# BlockDiagram.net
KiCad netlist of a schematic drawn in Altium Designer
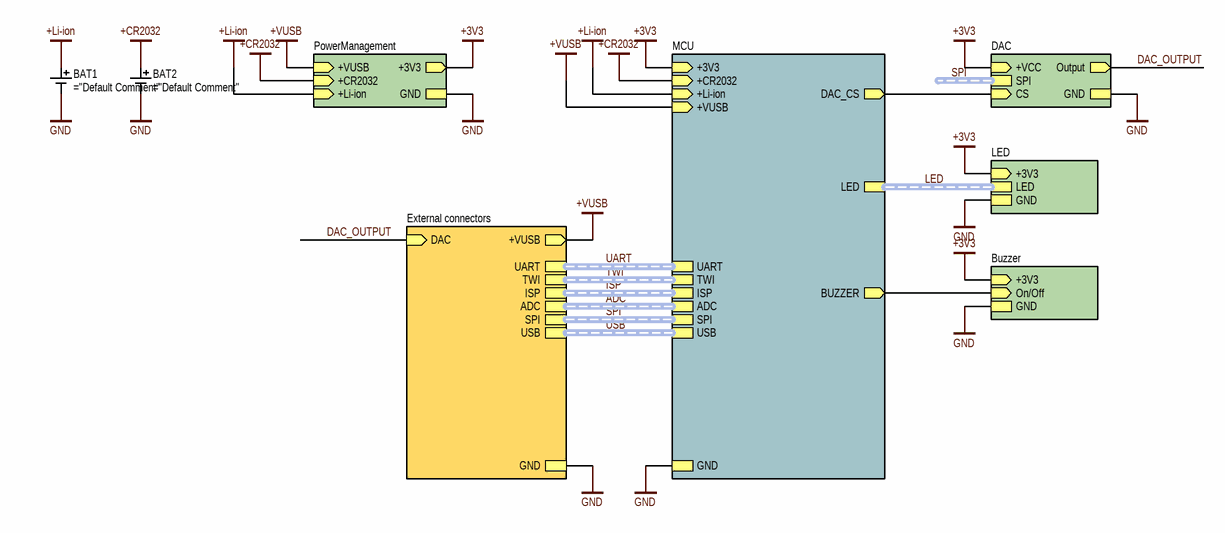
[diagram p0: BlockDiagram.SchDoc]

(export (version "E")
  (design (tool "Eeschema 10.0.6"))
  (components
    (comp (ref "BAT1")
      (value "~")
      (description "CONN HEADER R/A 2POS 2MM")
      (fields (field (name "TOLERANCE") "* %") (field (name "MANUFACTURER") "JST Sales America Inc."))
      (libsource (lib "femtoino") (part "S2B-PH-K-S(LF)(SN)"))
    )
    (comp (ref "BAT2")
      (value "~")
      (description "BATT HOLDER COIN 20MM 1 CELL SMD")
      (fields
        (field (name "TOLERANCE") "* %")
        (field (name "MANUFACTURER") "MPD (Memory Protection Devices)")
      )
      (libsource (lib "femtoino") (part "BU2032SM-HD-G"))
    )
  )
  (nets
    (net (code "9") (name "+CR2032") (class "Default")
      (node (ref "BAT2") (pin "POS") (pinfunction "POS_POS") (pintype "passive"))
    )
    (net (code "10") (name "+Li-ion") (class "Default")
      (node (ref "BAT1") (pin "POS") (pinfunction "POS_POS") (pintype "passive"))
    )
    (net (code "22") (name "GND") (class "Default")
      (node (ref "BAT1") (pin "NEG") (pinfunction "NEG_NEG") (pintype "passive"))
      (node (ref "BAT2") (pin "NEG") (pinfunction "NEG_NEG") (pintype "passive"))
    )
  )
)
